# MD070B_INTERFACE.net
KiCad netlist of a schematic drawn in Altium Designer
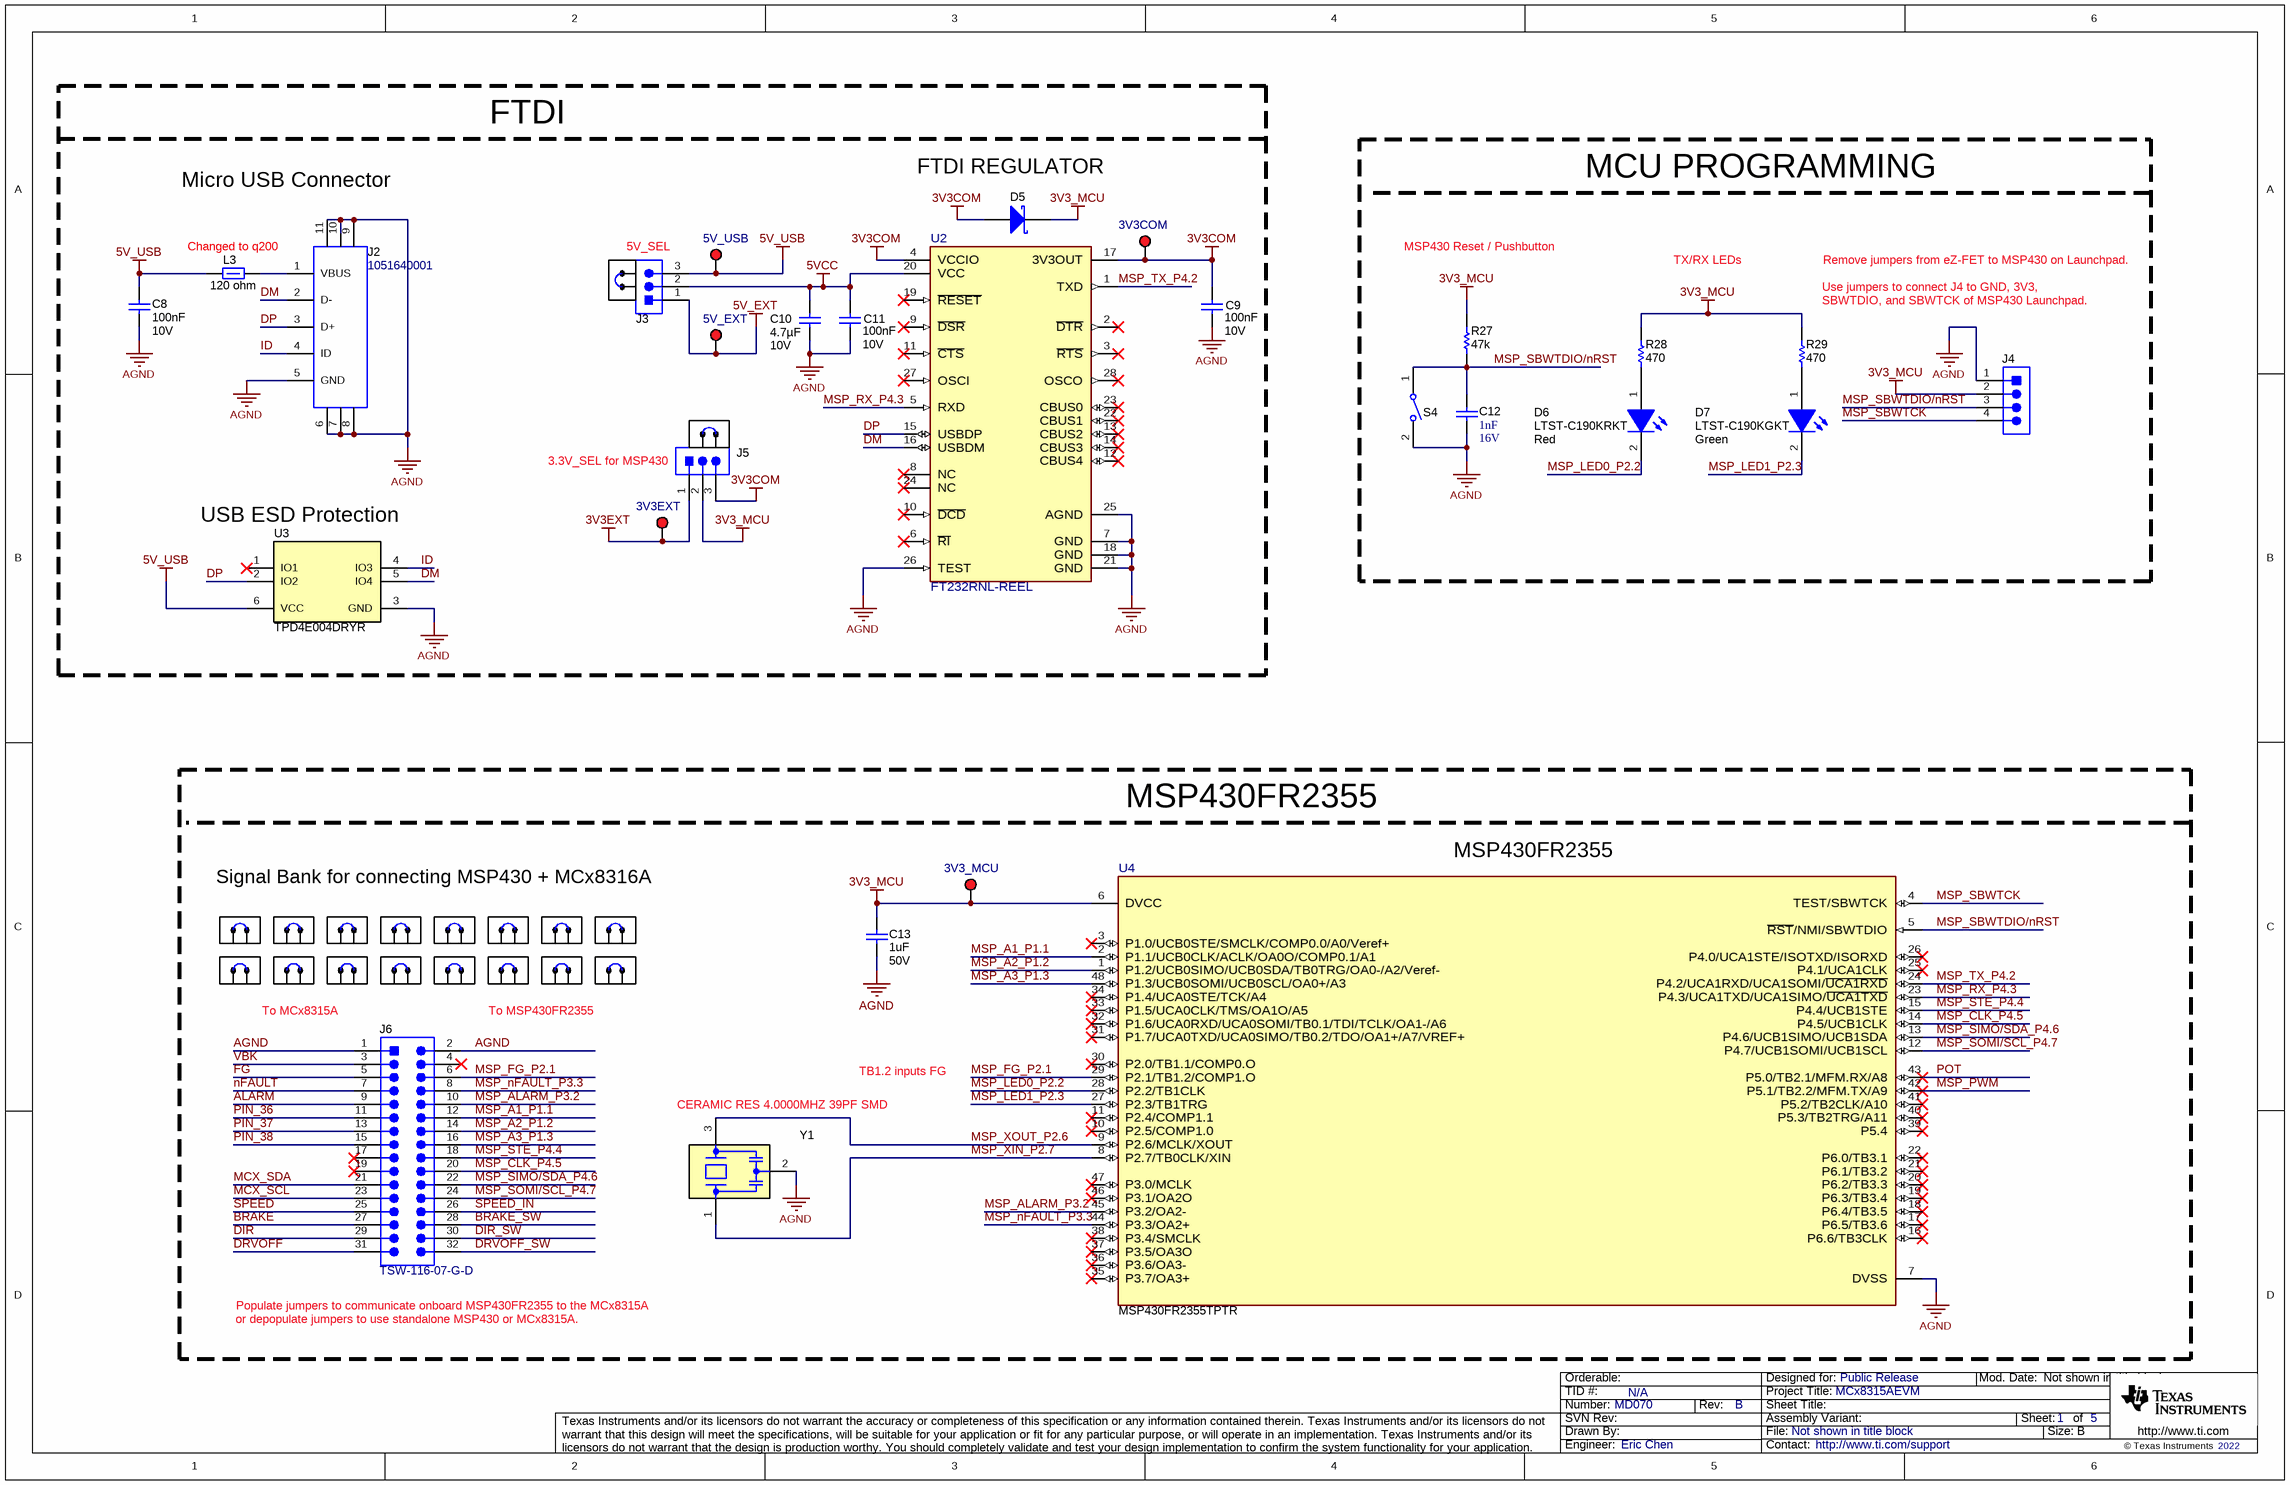
[diagram p0: MD070B_INTERFACE.SchDoc]

(export (version "E")
  (design (tool "Eeschema 10.0.6"))
  (components
    (comp (ref "C8")
      (value "0603ZC104KAT2A")
      (footprint "0603L")
      (description "CAP, CERM, 0.1 uF, 10 V, +/- 10%, X7R, 0603")
      (fields
        (field (name "MANUFACTURER") "AVX")
        (field (name "CAP_F") "100nF")
        (field (name "VDC_V") "10V")
        (field (name "PUBLISHER") "Texas Instruments")
      )
      (libsource (lib "Altium Vault - TI") (part "Capacitor"))
    )
    (comp (ref "C9")
      (value "0603ZC104KAT2A")
      (footprint "0603L")
      (description "CAP, CERM, 0.1 uF, 10 V, +/- 10%, X7R, 0603")
      (fields
        (field (name "MANUFACTURER") "AVX")
        (field (name "CAP_F") "100nF")
        (field (name "VDC_V") "10V")
        (field (name "PUBLISHER") "Texas Instruments")
      )
      (libsource (lib "Altium Vault - TI") (part "Capacitor"))
    )
    (comp (ref "C10")
      (value "GRM188Z71A475ME15D")
      (footprint "0603L")
      (description "CAP, CERM, 4.7 uF, 10 V, +/- 20%, X7R, 0603")
      (fields
        (field (name "MANUFACTURER") "MuRata")
        (field (name "CAP_F") "4.7µF")
        (field (name "VDC_V") "10V")
        (field (name "PUBLISHER") "Texas Instruments")
      )
      (libsource (lib "Altium Vault - TI") (part "Capacitor"))
    )
    (comp (ref "C11")
      (value "0603ZC104KAT2A")
      (footprint "0603L")
      (description "CAP, CERM, 0.1 uF, 10 V, +/- 10%, X7R, 0603")
      (fields
        (field (name "MANUFACTURER") "AVX")
        (field (name "CAP_F") "100nF")
        (field (name "VDC_V") "10V")
        (field (name "PUBLISHER") "Texas Instruments")
      )
      (libsource (lib "Altium Vault - TI") (part "Capacitor"))
    )
    (comp (ref "C12")
      (value "885012206034")
      (footprint "0603L")
      (description "CAP, CERM, 1000 pF, 16 V, +/- 10%, X7R, 0603")
      (fields
        (field (name "MANUFACTURER") "Wurth Elektronik")
        (field (name "CAP_F") "1nF")
        (field (name "VDC_V") "16V")
        (field (name "PUBLISHER") "Texas Instruments")
      )
      (libsource (lib "Altium Vault - TI") (part "Capacitor"))
    )
    (comp (ref "C13")
      (value "885012207103")
      (footprint "0805L")
      (description "CAP, CERM, 1 uF, 50 V, +/- 10%, X7R, 0805")
      (fields
        (field (name "VALUEDISPLAYED") "1uF")
        (field (name "MANUFACTURER") "Wurth Elektronik")
        (field (name "VDC_V") "50V")
        (field (name "PUBLISHER") "Texas Instruments")
      )
      (libsource (lib "Altium Vault - TI") (part "CMP-0007696-2"))
    )
    (comp (ref "D5")
      (value "BAT165E6327HTSA1")
      (footprint "SOD-323")
      (description "Diode, Schottky, 40 V, 0.75 A, AEC-Q101, SOD-323")
      (fields (field (name "MANUFACTURER") "Infineon Technologies"))
      (libsource (lib "Altium Vault - TI") (part "DIODE_SCHOTTKY"))
    )
    (comp (ref "D6")
      (value "LTST-C190KRKT")
      (footprint "LED_LTST-C190_Red")
      (description "LED, Red, SMD")
      (fields (field (name "ALTIUM_VALUE") "Red") (field (name "MANUFACTURER") "Lite-On"))
      (libsource (lib "Altium Vault - TI") (part "LED"))
    )
    (comp (ref "D7")
      (value "LTST-C190KGKT")
      (footprint "LED_LTST-C190_G")
      (description "LED, Green, SMD")
      (fields (field (name "ALTIUM_VALUE") "Green") (field (name "MANUFACTURER") "Lite-On"))
      (libsource (lib "Altium Vault - TI") (part "LED"))
    )
    (comp (ref "J2")
      (value "1051640001")
      (footprint "Molex_1051640001")
      (description "Receptacle, USB 2.0, Micro B, 5 Position, R/A, SMT")
      (fields (field (name "MANUFACTURER") "Molex") (field (name "PUBLISHER") "Texas Instruments"))
      (libsource (lib "Altium Vault - TI") (part "CONN_USB_MicroMini_6Shld"))
    )
    (comp (ref "J3")
      (value "Header_3x1")
      (footprint "PBC03SAAN")
      (description "Header, 100mil, 3x1, Gold, TH")
      (fields
        (field (name "PARTNUMBER") "PBC03SAAN")
        (field (name "MANUFACTURER") "Sullins Connector Solutions")
        (field (name "PUBLISHER") "Texas Instruments")
      )
      (libsource (lib "Altium Vault - TI") (part "CMP-0002334-1"))
    )
    (comp (ref "J4")
      (value "TSW-104-07-G-S")
      (footprint "TSW-104-07-G-S")
      (description "Header, 100mil, 4x1, Gold, TH")
      (fields (field (name "MANUFACTURER") "Samtec"))
      (libsource (lib "Altium Vault - TI") (part "Header_4x1"))
    )
    (comp (ref "J5")
      (value "Header_3x1")
      (footprint "PBC03SAAN")
      (description "Header, 100mil, 3x1, Gold, TH")
      (fields
        (field (name "PARTNUMBER") "PBC03SAAN")
        (field (name "MANUFACTURER") "Sullins Connector Solutions")
        (field (name "PUBLISHER") "Texas Instruments")
      )
      (libsource (lib "") (part "CMP-0002334-1_1"))
    )
    (comp (ref "J6")
      (value "TSW-116-07-G-D")
      (footprint "TSW-116-07-G-D")
      (description "Header, 100mil, 16x2, Gold, TH")
      (fields (field (name "MANUFACTURER") "Samtec") (field (name "PUBLISHER") "Texas Instruments"))
      (libsource (lib "Altium Vault - TI") (part "Header_16x2"))
    )
    (comp (ref "L3")
      (value "BLM18SG121TZ1D")
      (footprint "0603L")
      (description "Inductor, Ferrite Bead, Ferrite, 3 A, 120 ohm, AEC-Q200 Grade 1, SMD")
      (fields (field (name "DCR_OHM") "120 ohm") (field (name "MANUFACTURER") "MuRata"))
      (libsource (lib "Altium Vault - TI") (part "Ferrite_Bead"))
    )
    (comp (ref "R27")
      (value "RC0603JR-0747KL")
      (footprint "0603L")
      (description "RES, 47 k, 5%, 0.1 W, 0603")
      (fields (field (name "MANUFACTURER") "Yageo") (field (name "VALUEDISPLAYED") "47k"))
      (libsource (lib "Altium Vault - TI") (part "Resistor"))
    )
    (comp (ref "R28")
      (value "RC0603JR-07470RL")
      (footprint "0603L")
      (description "RES, 470, 5%, 0.1 W, 0603")
      (fields (field (name "MANUFACTURER") "Yageo") (field (name "VALUEDISPLAYED") "470"))
      (libsource (lib "Altium Vault - TI") (part "Resistor"))
    )
    (comp (ref "R29")
      (value "RC0603JR-07470RL")
      (footprint "0603L")
      (description "RES, 470, 5%, 0.1 W, 0603")
      (fields (field (name "MANUFACTURER") "Yageo") (field (name "VALUEDISPLAYED") "470"))
      (libsource (lib "Altium Vault - TI") (part "Resistor"))
    )
    (comp (ref "S4")
      (value "SW_SPST-single")
      (footprint "SW_434121025816")
      (description "Switch, Tactile, SPST, 12 V, SMD")
      (fields
        (field (name "PARTNUMBER") "434121025816")
        (field (name "MANUFACTURER") "Wurth Elektronik")
        (field (name "PUBLISHER") "Texas Instruments")
      )
      (libsource (lib "Altium Vault - TI") (part "SW_SPST-single"))
    )
    (comp (ref "SH-J2")
      (value "SNT-100-BK-G")
      (footprint "SNT-100-BK-G")
      (description "Shunt, 100mil, Gold plated, Black")
      (fields (field (name "ALTERNATE PARTNUMBER") "969102-0000-DA") (field (name "MANUFACTURER") "Samtec"))
      (libsource (lib "") (part "Shunt_1"))
    )
    (comp (ref "SH-J3")
      (value "SNT-100-BK-G")
      (footprint "SNT-100-BK-G")
      (description "Shunt, 100mil, Gold plated, Black")
      (fields (field (name "ALTERNATE PARTNUMBER") "969102-0000-DA") (field (name "MANUFACTURER") "Samtec"))
      (libsource (lib "Altium Vault - TI") (part "Shunt"))
    )
    (comp (ref "SH-J4")
      (value "SNT-100-BK-G")
      (footprint "SNT-100-BK-G")
      (description "Shunt, 100mil, Gold plated, Black")
      (fields (field (name "ALTERNATE PARTNUMBER") "969102-0000-DA") (field (name "MANUFACTURER") "Samtec"))
      (libsource (lib "Altium Vault - TI") (part "Shunt"))
    )
    (comp (ref "SH-J5")
      (value "SNT-100-BK-G")
      (footprint "SNT-100-BK-G")
      (description "Shunt, 100mil, Gold plated, Black")
      (fields (field (name "ALTERNATE PARTNUMBER") "969102-0000-DA") (field (name "MANUFACTURER") "Samtec"))
      (libsource (lib "Altium Vault - TI") (part "Shunt"))
    )
    (comp (ref "SH-J6")
      (value "SNT-100-BK-G")
      (footprint "SNT-100-BK-G")
      (description "Shunt, 100mil, Gold plated, Black")
      (fields (field (name "ALTERNATE PARTNUMBER") "969102-0000-DA") (field (name "MANUFACTURER") "Samtec"))
      (libsource (lib "Altium Vault - TI") (part "Shunt"))
    )
    (comp (ref "SH-J7")
      (value "SNT-100-BK-G")
      (footprint "SNT-100-BK-G")
      (description "Shunt, 100mil, Gold plated, Black")
      (fields (field (name "ALTERNATE PARTNUMBER") "969102-0000-DA") (field (name "MANUFACTURER") "Samtec"))
      (libsource (lib "Altium Vault - TI") (part "Shunt"))
    )
    (comp (ref "SH-J8")
      (value "SNT-100-BK-G")
      (footprint "SNT-100-BK-G")
      (description "Shunt, 100mil, Gold plated, Black")
      (fields (field (name "ALTERNATE PARTNUMBER") "969102-0000-DA") (field (name "MANUFACTURER") "Samtec"))
      (libsource (lib "Altium Vault - TI") (part "Shunt"))
    )
    (comp (ref "SH-J9")
      (value "SNT-100-BK-G")
      (footprint "SNT-100-BK-G")
      (description "Shunt, 100mil, Gold plated, Black")
      (fields (field (name "ALTERNATE PARTNUMBER") "969102-0000-DA") (field (name "MANUFACTURER") "Samtec"))
      (libsource (lib "Altium Vault - TI") (part "Shunt"))
    )
    (comp (ref "SH-J10")
      (value "SNT-100-BK-G")
      (footprint "SNT-100-BK-G")
      (description "Shunt, 100mil, Gold plated, Black")
      (fields (field (name "ALTERNATE PARTNUMBER") "969102-0000-DA") (field (name "MANUFACTURER") "Samtec"))
      (libsource (lib "Altium Vault - TI") (part "Shunt"))
    )
    (comp (ref "SH-J11")
      (value "SNT-100-BK-G")
      (footprint "SNT-100-BK-G")
      (description "Shunt, 100mil, Gold plated, Black")
      (fields (field (name "ALTERNATE PARTNUMBER") "969102-0000-DA") (field (name "MANUFACTURER") "Samtec"))
      (libsource (lib "Altium Vault - TI") (part "Shunt"))
    )
    (comp (ref "SH-J12")
      (value "SNT-100-BK-G")
      (footprint "SNT-100-BK-G")
      (description "Shunt, 100mil, Gold plated, Black")
      (fields (field (name "ALTERNATE PARTNUMBER") "969102-0000-DA") (field (name "MANUFACTURER") "Samtec"))
      (libsource (lib "Altium Vault - TI") (part "Shunt"))
    )
    (comp (ref "SH-J13")
      (value "SNT-100-BK-G")
      (footprint "SNT-100-BK-G")
      (description "Shunt, 100mil, Gold plated, Black")
      (fields (field (name "ALTERNATE PARTNUMBER") "969102-0000-DA") (field (name "MANUFACTURER") "Samtec"))
      (libsource (lib "Altium Vault - TI") (part "Shunt"))
    )
    (comp (ref "SH-J14")
      (value "SNT-100-BK-G")
      (footprint "SNT-100-BK-G")
      (description "Shunt, 100mil, Gold plated, Black")
      (fields (field (name "ALTERNATE PARTNUMBER") "969102-0000-DA") (field (name "MANUFACTURER") "Samtec"))
      (libsource (lib "Altium Vault - TI") (part "Shunt"))
    )
    (comp (ref "SH-J15")
      (value "SNT-100-BK-G")
      (footprint "SNT-100-BK-G")
      (description "Shunt, 100mil, Gold plated, Black")
      (fields (field (name "ALTERNATE PARTNUMBER") "969102-0000-DA") (field (name "MANUFACTURER") "Samtec"))
      (libsource (lib "Altium Vault - TI") (part "Shunt"))
    )
    (comp (ref "SH-J16")
      (value "SNT-100-BK-G")
      (footprint "SNT-100-BK-G")
      (description "Shunt, 100mil, Gold plated, Black")
      (fields (field (name "ALTERNATE PARTNUMBER") "969102-0000-DA") (field (name "MANUFACTURER") "Samtec"))
      (libsource (lib "Altium Vault - TI") (part "Shunt"))
    )
    (comp (ref "SH-J17")
      (value "SNT-100-BK-G")
      (footprint "SNT-100-BK-G")
      (description "Shunt, 100mil, Gold plated, Black")
      (fields (field (name "ALTERNATE PARTNUMBER") "969102-0000-DA") (field (name "MANUFACTURER") "Samtec"))
      (libsource (lib "Altium Vault - TI") (part "Shunt"))
    )
    (comp (ref "SH-J18")
      (value "SNT-100-BK-G")
      (footprint "SNT-100-BK-G")
      (description "Shunt, 100mil, Gold plated, Black")
      (fields (field (name "ALTERNATE PARTNUMBER") "969102-0000-DA") (field (name "MANUFACTURER") "Samtec"))
      (libsource (lib "Altium Vault - TI") (part "Shunt"))
    )
    (comp (ref "SH-J19")
      (value "SNT-100-BK-G")
      (footprint "SNT-100-BK-G")
      (description "Shunt, 100mil, Gold plated, Black")
      (fields (field (name "ALTERNATE PARTNUMBER") "969102-0000-DA") (field (name "MANUFACTURER") "Samtec"))
      (libsource (lib "Altium Vault - TI") (part "Shunt"))
    )
    (comp (ref "TP18")
      (value "3V3COM")
      (footprint "Keystone5000")
      (description "Test Point, Miniature, Red, TH")
      (fields
        (field (name "PARTNUMBER") "5000")
        (field (name "MANUFACTURER") "Keystone")
        (field (name "PUBLISHER") "Texas Instruments")
      )
      (libsource (lib "Altium Vault - TI") (part "CMP-0055137-1"))
    )
    (comp (ref "TP19")
      (value "5V_USB")
      (footprint "Keystone5000")
      (description "Test Point, Miniature, Red, TH")
      (fields
        (field (name "PARTNUMBER") "5000")
        (field (name "MANUFACTURER") "Keystone")
        (field (name "PUBLISHER") "Texas Instruments")
      )
      (libsource (lib "Altium Vault - TI") (part "CMP-0055137-1"))
    )
    (comp (ref "TP20")
      (value "5V_EXT")
      (footprint "Keystone5000")
      (description "Test Point, Miniature, Red, TH")
      (fields
        (field (name "PARTNUMBER") "5000")
        (field (name "MANUFACTURER") "Keystone")
        (field (name "PUBLISHER") "Texas Instruments")
      )
      (libsource (lib "Altium Vault - TI") (part "CMP-0055137-1"))
    )
    (comp (ref "TP21")
      (value "3V3EXT")
      (footprint "Keystone5000")
      (description "Test Point, Miniature, Red, TH")
      (fields
        (field (name "PARTNUMBER") "5000")
        (field (name "MANUFACTURER") "Keystone")
        (field (name "PUBLISHER") "Texas Instruments")
      )
      (libsource (lib "Altium Vault - TI") (part "CMP-0055137-1"))
    )
    (comp (ref "TP22")
      (value "3V3_MCU")
      (footprint "Keystone5000")
      (description "Test Point, Miniature, Red, TH")
      (fields
        (field (name "PARTNUMBER") "5000")
        (field (name "MANUFACTURER") "Keystone")
        (field (name "PUBLISHER") "Texas Instruments")
      )
      (libsource (lib "Altium Vault - TI") (part "CMP-0055137-1"))
    )
    (comp (ref "U2")
      (value "FT232RNL-REEL")
      (footprint "FP-FT232RNL-REEL_SSOP28-MFG")
      (description "UART Interface IC USB Full Speed to Serial UART IC, Includes Oscillator and EEPROM, SSOP-28")
      (fields
        (field (name "MANUFACTURER") "FTDI")
        (field (name "DIGIKEY PART NUMBER") "768-FT232RNL-REELCT-ND")
      )
      (libsource (lib "Altium Vault - TI") (part "SYM-FT232RNL-REEL"))
    )
    (comp (ref "U3")
      (value "TPD4E004DRYR")
      (footprint "DRY0006A")
      (description "4-Channel ESD Protection Array for High-Speed Data Interfaces, DRY0006A (USON-6)")
      (fields (field (name "MANUFACTURER") "Texas Instruments") (field (name "PARTNUMBER") "TPD4E004DRYR"))
      (libsource (lib "Altium Vault - TI") (part "TI-TPD4E004-SON_DRY-6"))
    )
    (comp (ref "U4")
      (value "MSP430FR2355TPTR")
      (footprint "PT0048A-MFG")
      (description "CPU16 MSP430™ FRAM Microcontroller IC 16-Bit 24MHz 32KB (32K x 8) FRAM 48-LQFP (7x7)")
      (fields
        (field (name "DIGIKEY PART NUMBER") "296-50261-1-ND")
        (field (name "MANUFACTURER") "Texas Instruments")
        (field (name "PARTNUMBER") "MSP430FR2355TPTR")
      )
      (libsource (lib "Altium Vault - TI") (part "SYM-MSP430FR2355TPTR"))
    )
    (comp (ref "Y1")
      (value "CSTCR4M00G55B-R0")
      (footprint "Murata_CSTCR_G")
      (description "Resonator, 4 MHz, 39 pF, AEC-Q200 Grade 1, SMD")
      (fields (field (name "MANUFACTURER") "MuRata"))
      (libsource (lib "Altium Vault - TI") (part "OSC_CSTCE"))
    )
  )
  (nets
    (net (code "1") (name "/ALARM") (class "Default")
      (node (ref "J6") (pin "9") (pinfunction "9_9") (pintype "passive"))
    )
    (net (code "2") (name "/BRAKE") (class "Default")
      (node (ref "J6") (pin "27") (pinfunction "27_27") (pintype "passive"))
    )
    (net (code "3") (name "/BRAKE_SW") (class "Default")
      (node (ref "J6") (pin "28") (pinfunction "28_28") (pintype "passive"))
    )
    (net (code "4") (name "/DIR") (class "Default")
      (node (ref "J6") (pin "29") (pinfunction "29_29") (pintype "passive"))
    )
    (net (code "5") (name "/DIR_SW") (class "Default")
      (node (ref "J6") (pin "30") (pinfunction "30_30") (pintype "passive"))
    )
    (net (code "6") (name "/DM") (class "Default")
      (node (ref "J2") (pin "2") (pinfunction "D-_2") (pintype "passive"))
      (node (ref "U2") (pin "16") (pinfunction "USBDM_16") (pintype "bidirectional"))
      (node (ref "U3") (pin "5") (pinfunction "IO4_5") (pintype "passive"))
    )
    (net (code "7") (name "/DP") (class "Default")
      (node (ref "J2") (pin "3") (pinfunction "D+_3") (pintype "passive"))
      (node (ref "U2") (pin "15") (pinfunction "USBDP_15") (pintype "bidirectional"))
      (node (ref "U3") (pin "2") (pinfunction "IO2_2") (pintype "passive"))
    )
    (net (code "8") (name "/DRVOFF") (class "Default")
      (node (ref "J6") (pin "31") (pinfunction "31_31") (pintype "passive"))
    )
    (net (code "9") (name "/DRVOFF_SW") (class "Default")
      (node (ref "J6") (pin "32") (pinfunction "32_32") (pintype "passive"))
    )
    (net (code "10") (name "/FG") (class "Default")
      (node (ref "J6") (pin "5") (pinfunction "5_5") (pintype "passive"))
    )
    (net (code "11") (name "/ID") (class "Default")
      (node (ref "J2") (pin "4") (pinfunction "ID_4") (pintype "passive"))
      (node (ref "U3") (pin "4") (pinfunction "IO3_4") (pintype "passive"))
    )
    (net (code "12") (name "/MCX_SCL") (class "Default")
      (node (ref "J6") (pin "23") (pinfunction "23_23") (pintype "passive"))
    )
    (net (code "13") (name "/MCX_SDA") (class "Default")
      (node (ref "J6") (pin "21") (pinfunction "21_21") (pintype "passive"))
    )
    (net (code "14") (name "/MSP_A1_P1.1") (class "Default")
      (node (ref "J6") (pin "12") (pinfunction "12_12") (pintype "passive"))
      (node (ref "U4") (pin "2") (pinfunction "P1.1/UCB0CLK/ACLK/OA0O/COMP0.1/A1_2") (pintype "bidirectional"))
    )
    (net (code "15") (name "/MSP_A2_P1.2") (class "Default")
      (node (ref "J6") (pin "14") (pinfunction "14_14") (pintype "passive"))
      (node (ref "U4") (pin "1") (pinfunction "P1.2/UCB0SIMO/UCB0SDA/TB0TRG/OA0-/A2/Veref-_1") (pintype "bidirectional"))
    )
    (net (code "16") (name "/MSP_A3_P1.3") (class "Default")
      (node (ref "J6") (pin "16") (pinfunction "16_16") (pintype "passive"))
      (node (ref "U4") (pin "48") (pinfunction "P1.3/UCB0SOMI/UCB0SCL/OA0+/A3_48") (pintype "bidirectional"))
    )
    (net (code "17") (name "/MSP_ALARM_P3.2") (class "Default")
      (node (ref "J6") (pin "10") (pinfunction "10_10") (pintype "passive"))
      (node (ref "U4") (pin "45") (pinfunction "P3.2/OA2-_45") (pintype "bidirectional"))
    )
    (net (code "18") (name "/MSP_CLK_P4.5") (class "Default")
      (node (ref "J6") (pin "20") (pinfunction "20_20") (pintype "passive"))
      (node (ref "U4") (pin "14") (pinfunction "P4.5/UCB1CLK_14") (pintype "bidirectional"))
    )
    (net (code "19") (name "/MSP_FG_P2.1") (class "Default")
      (node (ref "J6") (pin "6") (pinfunction "6_6") (pintype "passive"))
      (node (ref "U4") (pin "29") (pinfunction "P2.1/TB1.2/COMP1.O_29") (pintype "bidirectional"))
    )
    (net (code "20") (name "/MSP_LED0_P2.2") (class "Default")
      (node (ref "D6") (pin "2") (pinfunction "K_2") (pintype "passive"))
      (node (ref "U4") (pin "28") (pinfunction "P2.2/TB1CLK_28") (pintype "bidirectional"))
    )
    (net (code "21") (name "/MSP_LED1_P2.3") (class "Default")
      (node (ref "D7") (pin "2") (pinfunction "K_2") (pintype "passive"))
      (node (ref "U4") (pin "27") (pinfunction "P2.3/TB1TRG_27") (pintype "bidirectional"))
    )
    (net (code "22") (name "/MSP_PWM") (class "Default")
      (node (ref "U4") (pin "42") (pinfunction "P5.1/TB2.2/MFM.TX/A9_42") (pintype "bidirectional+no_connect"))
    )
    (net (code "23") (name "/MSP_RX_P4.3") (class "Default")
      (node (ref "U2") (pin "5") (pinfunction "RXD_5") (pintype "input"))
      (node (ref "U4") (pin "23") (pinfunction "P4.3/UCA1TXD/UCA1SIMO/~{UCA1TXD}_23") (pintype "bidirectional"))
    )
    (net (code "24") (name "/MSP_SBWTCK") (class "Default")
      (node (ref "J4") (pin "4") (pinfunction "4_4") (pintype "passive"))
      (node (ref "U4") (pin "4") (pinfunction "TEST/SBWTCK_4") (pintype "bidirectional"))
    )
    (net (code "25") (name "/MSP_SBWTDIO{slash}nRST") (class "Default")
      (node (ref "C12") (pin "1") (pinfunction "1_1") (pintype "passive"))
      (node (ref "J4") (pin "3") (pinfunction "3_3") (pintype "passive"))
      (node (ref "R27") (pin "1") (pinfunction "1_1") (pintype "passive"))
      (node (ref "S4") (pin "1") (pinfunction "1_1") (pintype "passive"))
      (node (ref "U4") (pin "5") (pinfunction "~{RST}/NMI/SBWTDIO_5") (pintype "input"))
    )
    (net (code "26") (name "/MSP_SIMO{slash}SDA_P4.6") (class "Default")
      (node (ref "J6") (pin "22") (pinfunction "22_22") (pintype "passive"))
      (node (ref "U4") (pin "13") (pinfunction "P4.6/UCB1SIMO/UCB1SDA_13") (pintype "bidirectional"))
    )
    (net (code "27") (name "/MSP_SOMI{slash}SCL_P4.7") (class "Default")
      (node (ref "J6") (pin "24") (pinfunction "24_24") (pintype "passive"))
      (node (ref "U4") (pin "12") (pinfunction "P4.7/UCB1SOMI/UCB1SCL_12") (pintype "bidirectional"))
    )
    (net (code "28") (name "/MSP_STE_P4.4") (class "Default")
      (node (ref "J6") (pin "18") (pinfunction "18_18") (pintype "passive"))
      (node (ref "U4") (pin "15") (pinfunction "P4.4/UCB1STE_15") (pintype "bidirectional"))
    )
    (net (code "29") (name "/MSP_TX_P4.2") (class "Default")
      (node (ref "U2") (pin "1") (pinfunction "TXD_1") (pintype "output"))
      (node (ref "U4") (pin "24") (pinfunction "P4.2/UCA1RXD/UCA1SOMI/~{UCA1RXD}_24") (pintype "bidirectional"))
    )
    (net (code "30") (name "/MSP_XIN_P2.7") (class "Default")
      (node (ref "U4") (pin "8") (pinfunction "P2.7/TB0CLK/XIN_8") (pintype "bidirectional"))
      (node (ref "Y1") (pin "1") (pinfunction "In_1") (pintype "passive"))
    )
    (net (code "31") (name "/MSP_XOUT_P2.6") (class "Default")
      (node (ref "U4") (pin "9") (pinfunction "P2.6/MCLK/XOUT_9") (pintype "bidirectional"))
      (node (ref "Y1") (pin "3") (pinfunction "Out_3") (pintype "passive"))
    )
    (net (code "32") (name "/MSP_nFAULT_P3.3") (class "Default")
      (node (ref "J6") (pin "8") (pinfunction "8_8") (pintype "passive"))
      (node (ref "U4") (pin "44") (pinfunction "P3.3/OA2+_44") (pintype "bidirectional"))
    )
    (net (code "33") (name "/PIN_36") (class "Default")
      (node (ref "J6") (pin "11") (pinfunction "11_11") (pintype "passive"))
    )
    (net (code "34") (name "/PIN_37") (class "Default")
      (node (ref "J6") (pin "13") (pinfunction "13_13") (pintype "passive"))
    )
    (net (code "35") (name "/PIN_38") (class "Default")
      (node (ref "J6") (pin "15") (pinfunction "15_15") (pintype "passive"))
    )
    (net (code "36") (name "/POT") (class "Default")
      (node (ref "U4") (pin "43") (pinfunction "P5.0/TB2.1/MFM.RX/A8_43") (pintype "bidirectional+no_connect"))
    )
    (net (code "37") (name "/SPEED") (class "Default")
      (node (ref "J6") (pin "25") (pinfunction "25_25") (pintype "passive"))
    )
    (net (code "38") (name "/SPEED_IN") (class "Default")
      (node (ref "J6") (pin "26") (pinfunction "26_26") (pintype "passive"))
    )
    (net (code "39") (name "/VBK") (class "Default")
      (node (ref "J6") (pin "3") (pinfunction "3_3") (pintype "passive"))
    )
    (net (code "40") (name "/nFAULT") (class "Default")
      (node (ref "J6") (pin "7") (pinfunction "7_7") (pintype "passive"))
    )
    (net (code "41") (name "3V3COM") (class "Default")
      (node (ref "C9") (pin "1") (pinfunction "1_1") (pintype "passive"))
      (node (ref "D5") (pin "2") (pinfunction "A_2") (pintype "passive"))
      (node (ref "J5") (pin "3") (pinfunction "3_3") (pintype "passive"))
      (node (ref "TP18") (pin "1") (pintype "passive"))
      (node (ref "U2") (pin "17") (pinfunction "3V3OUT_17") (pintype "power_in"))
      (node (ref "U2") (pin "4") (pinfunction "VCCIO_4") (pintype "power_in"))
    )
    (net (code "42") (name "3V3EXT") (class "Default")
      (node (ref "J5") (pin "1") (pinfunction "1_1") (pintype "passive"))
      (node (ref "TP21") (pin "1") (pintype "passive"))
    )
    (net (code "43") (name "3V3_MCU") (class "Default")
      (node (ref "C13") (pin "1") (pinfunction "1_1") (pintype "passive"))
      (node (ref "D5") (pin "1") (pinfunction "K_1") (pintype "passive"))
      (node (ref "J4") (pin "2") (pinfunction "2_2") (pintype "passive"))
      (node (ref "J5") (pin "2") (pinfunction "2_2") (pintype "passive"))
      (node (ref "R27") (pin "2") (pinfunction "2_2") (pintype "passive"))
      (node (ref "R28") (pin "2") (pinfunction "2_2") (pintype "passive"))
      (node (ref "R29") (pin "2") (pinfunction "2_2") (pintype "passive"))
      (node (ref "TP22") (pin "1") (pintype "passive"))
      (node (ref "U4") (pin "6") (pinfunction "DVCC_6") (pintype "power_in"))
    )
    (net (code "44") (name "5VCC") (class "Default")
      (node (ref "C10") (pin "2") (pinfunction "2_2") (pintype "passive"))
      (node (ref "C11") (pin "1") (pinfunction "1_1") (pintype "passive"))
      (node (ref "J3") (pin "2") (pinfunction "2_2") (pintype "passive"))
      (node (ref "U2") (pin "20") (pinfunction "VCC_20") (pintype "power_in"))
    )
    (net (code "45") (name "5V_EXT") (class "Default")
      (node (ref "J3") (pin "1") (pinfunction "1_1") (pintype "passive"))
      (node (ref "TP20") (pin "1") (pintype "passive"))
    )
    (net (code "46") (name "5V_USB") (class "Default")
      (node (ref "C8") (pin "1") (pinfunction "1_1") (pintype "passive"))
      (node (ref "J3") (pin "3") (pinfunction "3_3") (pintype "passive"))
      (node (ref "L3") (pin "1") (pinfunction "1_1") (pintype "passive"))
      (node (ref "TP19") (pin "1") (pintype "passive"))
      (node (ref "U3") (pin "6") (pinfunction "VCC_6") (pintype "power_in"))
    )
    (net (code "47") (name "AGND") (class "Default")
      (node (ref "C10") (pin "1") (pinfunction "1_1") (pintype "passive"))
      (node (ref "C11") (pin "2") (pinfunction "2_2") (pintype "passive"))
      (node (ref "C12") (pin "2") (pinfunction "2_2") (pintype "passive"))
      (node (ref "C13") (pin "2") (pinfunction "2_2") (pintype "passive"))
      (node (ref "C8") (pin "2") (pinfunction "2_2") (pintype "passive"))
      (node (ref "C9") (pin "2") (pinfunction "2_2") (pintype "passive"))
      (node (ref "J2") (pin "10") (pinfunction "10_10") (pintype "passive"))
      (node (ref "J2") (pin "11") (pinfunction "11_11") (pintype "passive"))
      (node (ref "J2") (pin "5") (pinfunction "GND_5") (pintype "passive"))
      (node (ref "J2") (pin "6") (pinfunction "6_6") (pintype "passive"))
      (node (ref "J2") (pin "7") (pinfunction "7_7") (pintype "passive"))
      (node (ref "J2") (pin "8") (pinfunction "8_8") (pintype "passive"))
      (node (ref "J2") (pin "9") (pinfunction "9_9") (pintype "passive"))
      (node (ref "J4") (pin "1") (pinfunction "1_1") (pintype "passive"))
      (node (ref "J6") (pin "1") (pinfunction "1_1") (pintype "passive"))
      (node (ref "J6") (pin "2") (pinfunction "2_2") (pintype "passive"))
      (node (ref "S4") (pin "2") (pinfunction "2_2") (pintype "passive"))
      (node (ref "U2") (pin "18") (pinfunction "GND_18") (pintype "power_in"))
      (node (ref "U2") (pin "21") (pinfunction "GND_21") (pintype "power_in"))
      (node (ref "U2") (pin "25") (pinfunction "AGND_25") (pintype "power_in"))
      (node (ref "U2") (pin "26") (pinfunction "TEST_26") (pintype "input"))
      (node (ref "U2") (pin "7") (pinfunction "GND_7") (pintype "power_in"))
      (node (ref "U3") (pin "3") (pinfunction "GND_3") (pintype "power_in"))
      (node (ref "U4") (pin "7") (pinfunction "DVSS_7") (pintype "power_in"))
      (node (ref "Y1") (pin "2") (pinfunction "GND_2") (pintype "passive"))
    )
    (net (code "48") (name "Net-(D6-A)") (class "Default")
      (node (ref "D6") (pin "1") (pinfunction "A_1") (pintype "passive"))
      (node (ref "R28") (pin "1") (pinfunction "1_1") (pintype "passive"))
    )
    (net (code "49") (name "Net-(D7-A)") (class "Default")
      (node (ref "D7") (pin "1") (pinfunction "A_1") (pintype "passive"))
      (node (ref "R29") (pin "1") (pinfunction "1_1") (pintype "passive"))
    )
    (net (code "50") (name "Net-(J2-VBUS)") (class "Default")
      (node (ref "J2") (pin "1") (pinfunction "VBUS_1") (pintype "passive"))
      (node (ref "L3") (pin "2") (pinfunction "2_2") (pintype "passive"))
    )
    (net (code "51") (name "unconnected-(J6-Pad4)") (class "Default")
      (node (ref "J6") (pin "4") (pinfunction "4_4") (pintype "passive+no_connect"))
    )
    (net (code "52") (name "unconnected-(J6-Pad17)") (class "Default")
      (node (ref "J6") (pin "17") (pinfunction "17_17") (pintype "passive+no_connect"))
    )
    (net (code "53") (name "unconnected-(J6-Pad19)") (class "Default")
      (node (ref "J6") (pin "19") (pinfunction "19_19") (pintype "passive+no_connect"))
    )
    (net (code "54") (name "unconnected-(U2-CBUS0-Pad23)") (class "Default")
      (node (ref "U2") (pin "23") (pinfunction "CBUS0_23") (pintype "bidirectional+no_connect"))
    )
    (net (code "55") (name "unconnected-(U2-CBUS1-Pad22)") (class "Default")
      (node (ref "U2") (pin "22") (pinfunction "CBUS1_22") (pintype "bidirectional+no_connect"))
    )
    (net (code "56") (name "unconnected-(U2-CBUS2-Pad13)") (class "Default")
      (node (ref "U2") (pin "13") (pinfunction "CBUS2_13") (pintype "bidirectional+no_connect"))
    )
    (net (code "57") (name "unconnected-(U2-CBUS3-Pad14)") (class "Default")
      (node (ref "U2") (pin "14") (pinfunction "CBUS3_14") (pintype "bidirectional+no_connect"))
    )
    (net (code "58") (name "unconnected-(U2-CBUS4-Pad12)") (class "Default")
      (node (ref "U2") (pin "12") (pinfunction "CBUS4_12") (pintype "bidirectional+no_connect"))
    )
    (net (code "59") (name "unconnected-(U2-NC-Pad8)") (class "Default")
      (node (ref "U2") (pin "8") (pinfunction "NC_8") (pintype "passive+no_connect"))
    )
    (net (code "60") (name "unconnected-(U2-NC-Pad24)") (class "Default")
      (node (ref "U2") (pin "24") (pinfunction "NC_24") (pintype "passive+no_connect"))
    )
    (net (code "61") (name "unconnected-(U2-OSCI-Pad27)") (class "Default")
      (node (ref "U2") (pin "27") (pinfunction "OSCI_27") (pintype "input+no_connect"))
    )
    (net (code "62") (name "unconnected-(U2-OSCO-Pad28)") (class "Default")
      (node (ref "U2") (pin "28") (pinfunction "OSCO_28") (pintype "output+no_connect"))
    )
    (net (code "63") (name "unconnected-(U2-~{CTS}-Pad11)") (class "Default")
      (node (ref "U2") (pin "11") (pinfunction "~{CTS}_11") (pintype "input+no_connect"))
    )
    (net (code "64") (name "unconnected-(U2-~{DCD}-Pad10)") (class "Default")
      (node (ref "U2") (pin "10") (pinfunction "~{DCD}_10") (pintype "input+no_connect"))
    )
    (net (code "65") (name "unconnected-(U2-~{DSR}-Pad9)") (class "Default")
      (node (ref "U2") (pin "9") (pinfunction "~{DSR}_9") (pintype "input+no_connect"))
    )
    (net (code "66") (name "unconnected-(U2-~{DTR}-Pad2)") (class "Default")
      (node (ref "U2") (pin "2") (pinfunction "~{DTR}_2") (pintype "output+no_connect"))
    )
    (net (code "67") (name "unconnected-(U2-~{RESET}-Pad19)") (class "Default")
      (node (ref "U2") (pin "19") (pinfunction "~{RESET}_19") (pintype "input+no_connect"))
    )
    (net (code "68") (name "unconnected-(U2-~{RI}-Pad6)") (class "Default")
      (node (ref "U2") (pin "6") (pinfunction "~{RI}_6") (pintype "input+no_connect"))
    )
    (net (code "69") (name "unconnected-(U2-~{RTS}-Pad3)") (class "Default")
      (node (ref "U2") (pin "3") (pinfunction "~{RTS}_3") (pintype "output+no_connect"))
    )
    (net (code "70") (name "unconnected-(U3-IO1-Pad1)") (class "Default")
      (node (ref "U3") (pin "1") (pinfunction "IO1_1") (pintype "passive+no_connect"))
    )
    (net (code "71") (name "unconnected-(U4-P1.0{slash}UCB0STE{slash}SMCLK{slash}COMP0.0{slash}A0{slash}Veref+-Pad3)") (class "Default")
      (node (ref "U4") (pin "3") (pinfunction "P1.0/UCB0STE/SMCLK/COMP0.0/A0/Veref+_3") (pintype "bidirectional+no_connect"))
    )
    (net (code "72") (name "unconnected-(U4-P1.4{slash}UCA0STE{slash}TCK{slash}A4-Pad34)") (class "Default")
      (node (ref "U4") (pin "34") (pinfunction "P1.4/UCA0STE/TCK/A4_34") (pintype "bidirectional+no_connect"))
    )
    (net (code "73") (name "unconnected-(U4-P1.5{slash}UCA0CLK{slash}TMS{slash}OA1O{slash}A5-Pad33)") (class "Default")
      (node (ref "U4") (pin "33") (pinfunction "P1.5/UCA0CLK/TMS/OA1O/A5_33") (pintype "bidirectional+no_connect"))
    )
    (net (code "74") (name "unconnected-(U4-P1.6{slash}UCA0RXD{slash}UCA0SOMI{slash}TB0.1{slash}TDI{slash}TCLK{slash}OA1-{slash}A6-Pad32)") (class "Default")
      (node (ref "U4") (pin "32") (pinfunction "P1.6/UCA0RXD/UCA0SOMI/TB0.1/TDI/TCLK/OA1-/A6_32") (pintype "bidirectional+no_connect"))
    )
    (net (code "75") (name "unconnected-(U4-P1.7{slash}UCA0TXD{slash}UCA0SIMO{slash}TB0.2{slash}TDO{slash}OA1+{slash}A7{slash}VREF+-Pad31)") (class "Default")
      (node (ref "U4") (pin "31") (pinfunction "P1.7/UCA0TXD/UCA0SIMO/TB0.2/TDO/OA1+/A7/VREF+_31") (pintype "bidirectional+no_connect"))
    )
    (net (code "76") (name "unconnected-(U4-P2.0{slash}TB1.1{slash}COMP0.O-Pad30)") (class "Default")
      (node (ref "U4") (pin "30") (pinfunction "P2.0/TB1.1/COMP0.O_30") (pintype "bidirectional+no_connect"))
    )
    (net (code "77") (name "unconnected-(U4-P2.4{slash}COMP1.1-Pad11)") (class "Default")
      (node (ref "U4") (pin "11") (pinfunction "P2.4/COMP1.1_11") (pintype "bidirectional+no_connect"))
    )
    (net (code "78") (name "unconnected-(U4-P2.5{slash}COMP1.0-Pad10)") (class "Default")
      (node (ref "U4") (pin "10") (pinfunction "P2.5/COMP1.0_10") (pintype "bidirectional+no_connect"))
    )
    (net (code "79") (name "unconnected-(U4-P3.0{slash}MCLK-Pad47)") (class "Default")
      (node (ref "U4") (pin "47") (pinfunction "P3.0/MCLK_47") (pintype "bidirectional+no_connect"))
    )
    (net (code "80") (name "unconnected-(U4-P3.1{slash}OA2O-Pad46)") (class "Default")
      (node (ref "U4") (pin "46") (pinfunction "P3.1/OA2O_46") (pintype "bidirectional+no_connect"))
    )
    (net (code "81") (name "unconnected-(U4-P3.4{slash}SMCLK-Pad38)") (class "Default")
      (node (ref "U4") (pin "38") (pinfunction "P3.4/SMCLK_38") (pintype "bidirectional+no_connect"))
    )
    (net (code "82") (name "unconnected-(U4-P3.5{slash}OA3O-Pad37)") (class "Default")
      (node (ref "U4") (pin "37") (pinfunction "P3.5/OA3O_37") (pintype "bidirectional+no_connect"))
    )
    (net (code "83") (name "unconnected-(U4-P3.6{slash}OA3--Pad36)") (class "Default")
      (node (ref "U4") (pin "36") (pinfunction "P3.6/OA3-_36") (pintype "bidirectional+no_connect"))
    )
    (net (code "84") (name "unconnected-(U4-P3.7{slash}OA3+-Pad35)") (class "Default")
      (node (ref "U4") (pin "35") (pinfunction "P3.7/OA3+_35") (pintype "bidirectional+no_connect"))
    )
    (net (code "85") (name "unconnected-(U4-P4.0{slash}UCA1STE{slash}ISOTXD{slash}ISORXD-Pad26)") (class "Default")
      (node (ref "U4") (pin "26") (pinfunction "P4.0/UCA1STE/ISOTXD/ISORXD_26") (pintype "bidirectional+no_connect"))
    )
    (net (code "86") (name "unconnected-(U4-P4.1{slash}UCA1CLK-Pad25)") (class "Default")
      (node (ref "U4") (pin "25") (pinfunction "P4.1/UCA1CLK_25") (pintype "bidirectional+no_connect"))
    )
    (net (code "87") (name "unconnected-(U4-P5.2{slash}TB2CLK{slash}A10-Pad41)") (class "Default")
      (node (ref "U4") (pin "41") (pinfunction "P5.2/TB2CLK/A10_41") (pintype "bidirectional+no_connect"))
    )
    (net (code "88") (name "unconnected-(U4-P5.3{slash}TB2TRG{slash}A11-Pad40)") (class "Default")
      (node (ref "U4") (pin "40") (pinfunction "P5.3/TB2TRG/A11_40") (pintype "bidirectional+no_connect"))
    )
    (net (code "89") (name "unconnected-(U4-P5.4-Pad39)") (class "Default")
      (node (ref "U4") (pin "39") (pinfunction "P5.4_39") (pintype "bidirectional+no_connect"))
    )
    (net (code "90") (name "unconnected-(U4-P6.0{slash}TB3.1-Pad22)") (class "Default")
      (node (ref "U4") (pin "22") (pinfunction "P6.0/TB3.1_22") (pintype "bidirectional+no_connect"))
    )
    (net (code "91") (name "unconnected-(U4-P6.1{slash}TB3.2-Pad21)") (class "Default")
      (node (ref "U4") (pin "21") (pinfunction "P6.1/TB3.2_21") (pintype "bidirectional+no_connect"))
    )
    (net (code "92") (name "unconnected-(U4-P6.2{slash}TB3.3-Pad20)") (class "Default")
      (node (ref "U4") (pin "20") (pinfunction "P6.2/TB3.3_20") (pintype "bidirectional+no_connect"))
    )
    (net (code "93") (name "unconnected-(U4-P6.3{slash}TB3.4-Pad19)") (class "Default")
      (node (ref "U4") (pin "19") (pinfunction "P6.3/TB3.4_19") (pintype "bidirectional+no_connect"))
    )
    (net (code "94") (name "unconnected-(U4-P6.4{slash}TB3.5-Pad18)") (class "Default")
      (node (ref "U4") (pin "18") (pinfunction "P6.4/TB3.5_18") (pintype "bidirectional+no_connect"))
    )
    (net (code "95") (name "unconnected-(U4-P6.5{slash}TB3.6-Pad17)") (class "Default")
      (node (ref "U4") (pin "17") (pinfunction "P6.5/TB3.6_17") (pintype "bidirectional+no_connect"))
    )
    (net (code "96") (name "unconnected-(U4-P6.6{slash}TB3CLK-Pad16)") (class "Default")
      (node (ref "U4") (pin "16") (pinfunction "P6.6/TB3CLK_16") (pintype "bidirectional+no_connect"))
    )
  )
)
